# Kameras.net
KiCad netlist of a schematic drawn in Altium Designer
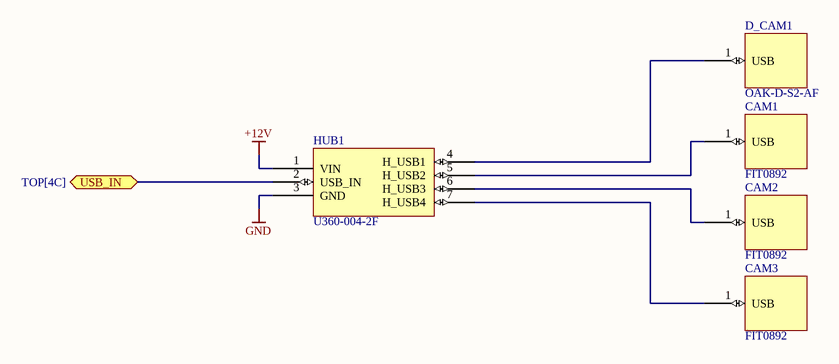
[diagram p0: Kameras.SchDoc]

(export (version "E")
  (design (tool "Eeschema 10.0.6"))
  (components
    (comp (ref "CAM1") (value "FIT0892") (libsource (lib "3D_Scanner") (part "USB Kamera")))
    (comp (ref "CAM2") (value "FIT0892") (libsource (lib "3D_Scanner") (part "USB Kamera")))
    (comp (ref "CAM3") (value "FIT0892") (libsource (lib "3D_Scanner") (part "USB Kamera")))
    (comp (ref "D_CAM1") (value "OAK-D-S2-AF") (libsource (lib "3D_Scanner") (part "Depth Kamera")))
    (comp (ref "HUB1")
      (value "U360-004-2F")
      (description "Interface Modules 4PT USB3.0 SSSPD HUB/CHARGER")
      (libsource (lib "3D_Scanner") (part "USB HUB"))
    )
  )
  (nets
    (net (code "1") (name "+12V") (class "Default")
      (node (ref "HUB1") (pin "1") (pinfunction "VIN_1") (pintype "power_in"))
    )
    (net (code "2") (name "/USB_IN") (class "Default")
      (node (ref "HUB1") (pin "2") (pinfunction "USB_IN_2") (pintype "bidirectional"))
    )
    (net (code "3") (name "GND") (class "Default")
      (node (ref "HUB1") (pin "3") (pinfunction "GND_3") (pintype "power_in"))
    )
    (net (code "4") (name "Net-(CAM1-USB)") (class "Default")
      (node (ref "CAM1") (pin "1") (pinfunction "USB_1") (pintype "bidirectional"))
      (node (ref "HUB1") (pin "5") (pinfunction "H_USB2_5") (pintype "bidirectional"))
    )
    (net (code "5") (name "Net-(CAM2-USB)") (class "Default")
      (node (ref "CAM2") (pin "1") (pinfunction "USB_1") (pintype "bidirectional"))
      (node (ref "HUB1") (pin "6") (pinfunction "H_USB3_6") (pintype "bidirectional"))
    )
    (net (code "6") (name "Net-(CAM3-USB)") (class "Default")
      (node (ref "CAM3") (pin "1") (pinfunction "USB_1") (pintype "bidirectional"))
      (node (ref "HUB1") (pin "7") (pinfunction "H_USB4_7") (pintype "bidirectional"))
    )
    (net (code "7") (name "Net-(D_CAM1-USB)") (class "Default")
      (node (ref "D_CAM1") (pin "1") (pinfunction "USB_1") (pintype "bidirectional"))
      (node (ref "HUB1") (pin "4") (pinfunction "H_USB1_4") (pintype "bidirectional"))
    )
  )
)
